# AlphanumericDisplay.net
KiCad netlist of a schematic drawn in EAGLE
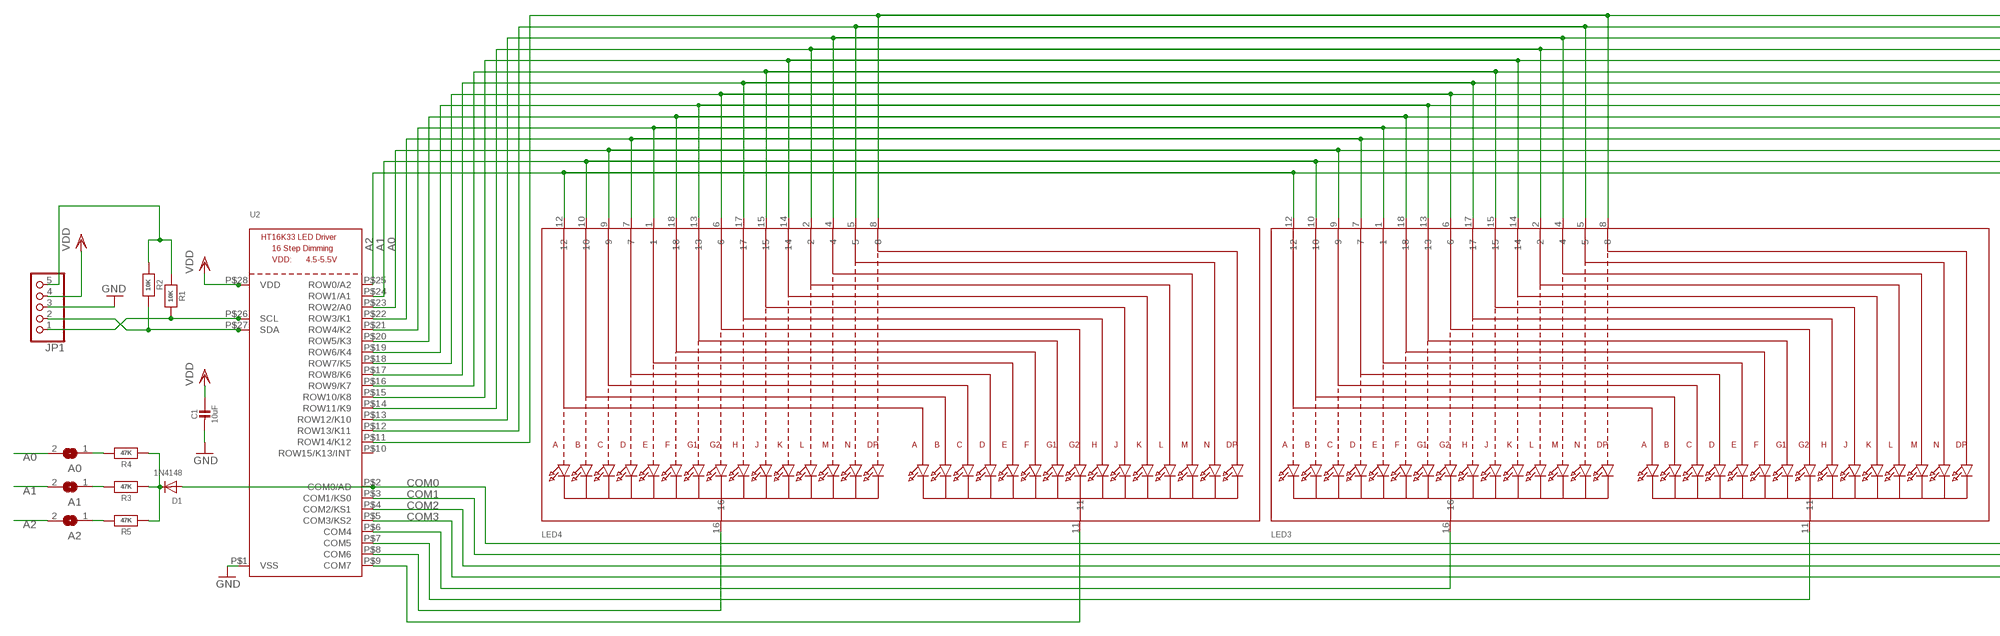
[diagram p0: schematic, sheet 1, part 1 of 2]
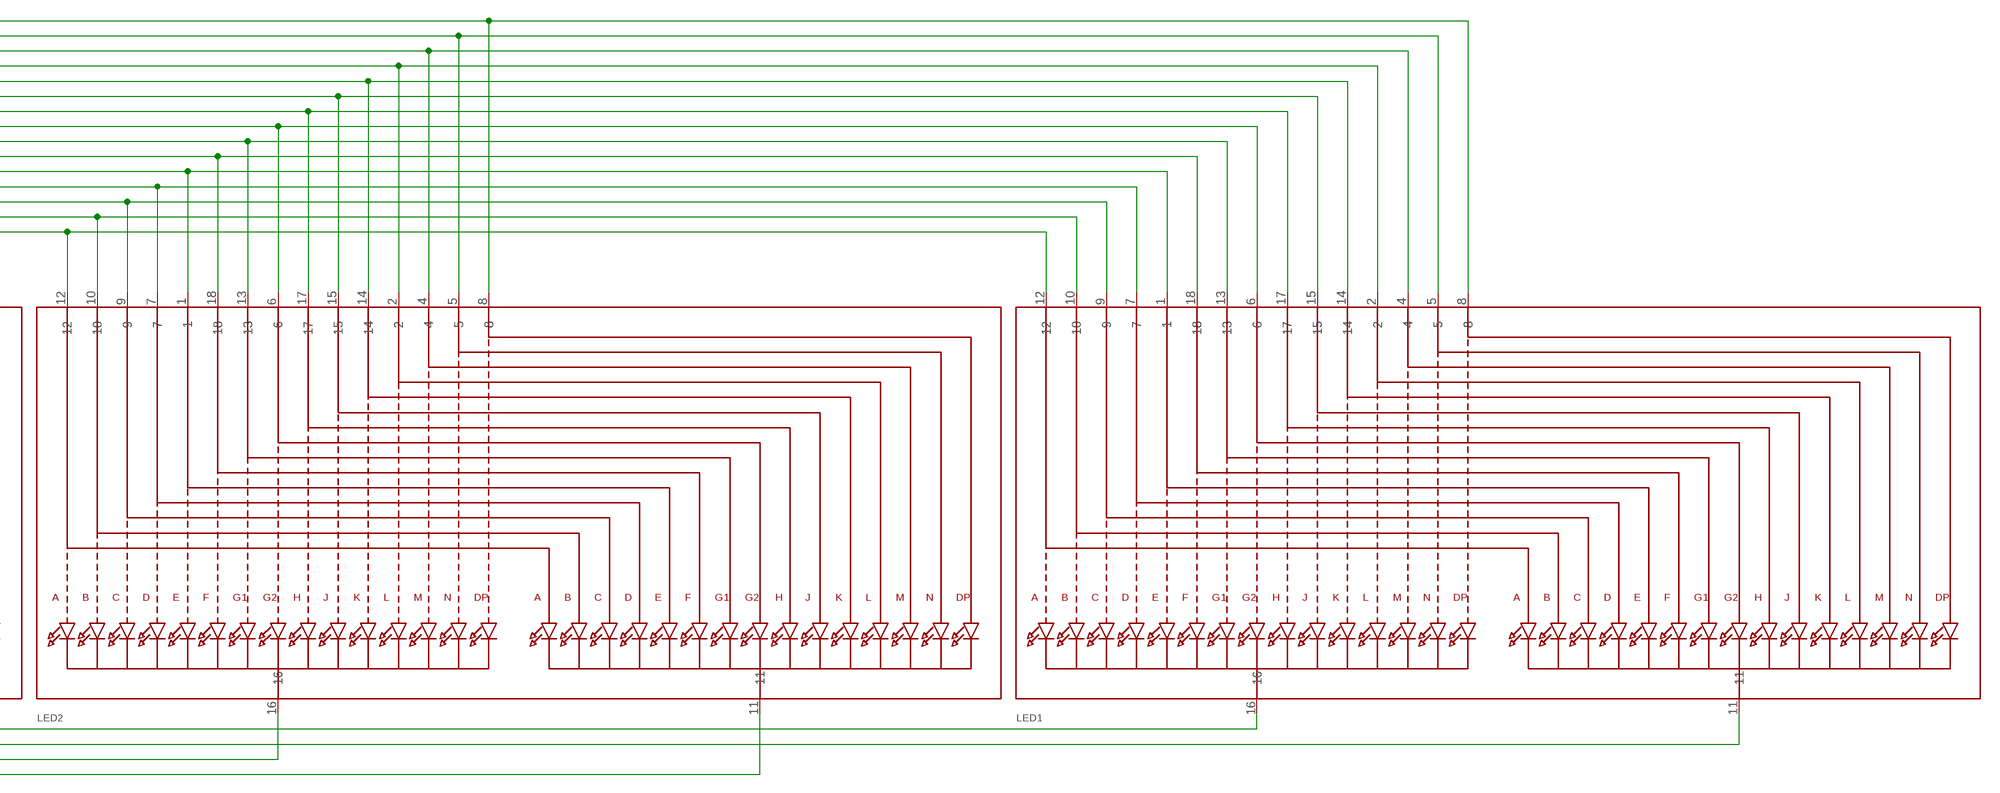
[diagram p1: schematic, sheet 1, part 2 of 2]

(export (version "E")
  (design (tool "Eeschema 10.0.6"))
  (components
    (comp (ref "A0")
      (value "SOLDERJUMPERREFLOW_NOPASTE")
      (footprint "eagle-import:SOLDERJUMPER_REFLOW_NOPASTE")
      (libsource (lib "eagle-import") (part "SOLDERJUMPERREFLOW_NOPASTE"))
    )
    (comp (ref "A1")
      (value "SOLDERJUMPERREFLOW_NOPASTE")
      (footprint "eagle-import:SOLDERJUMPER_REFLOW_NOPASTE")
      (libsource (lib "eagle-import") (part "SOLDERJUMPERREFLOW_NOPASTE"))
    )
    (comp (ref "A2")
      (value "SOLDERJUMPERREFLOW_NOPASTE")
      (footprint "eagle-import:SOLDERJUMPER_REFLOW_NOPASTE")
      (libsource (lib "eagle-import") (part "SOLDERJUMPERREFLOW_NOPASTE"))
    )
    (comp (ref "C1")
      (value "10uF")
      (footprint "eagle-import:0805-NO")
      (libsource (lib "eagle-import") (part "CAP_CERAMIC0805-NOOUTLINE"))
    )
    (comp (ref "D1")
      (value "1N4148")
      (footprint "eagle-import:SOD-323F")
      (libsource (lib "eagle-import") (part "DIODESOD-323F"))
    )
    (comp (ref "JP1")
      (value "HEADER-1X570MIL")
      (footprint "eagle-import:1X05_ROUND_70")
      (libsource (lib "eagle-import") (part "HEADER-1X570MIL"))
    )
    (comp (ref "LED1")
      (value "DISP_SEGMENT_STARBURST_DUAL_COMMONCATHODE")
      (footprint "eagle-import:SEGMENT_STARTBUST_DUAL_KWA-541CBB")
      (libsource (lib "eagle-import") (part "DISP_SEGMENT_STARBURST_DUAL_COMMONCATHODE"))
    )
    (comp (ref "LED2")
      (value "DISP_SEGMENT_STARBURST_DUAL_COMMONCATHODE")
      (footprint "eagle-import:SEGMENT_STARTBUST_DUAL_KWA-541CBB")
      (libsource (lib "eagle-import") (part "DISP_SEGMENT_STARBURST_DUAL_COMMONCATHODE"))
    )
    (comp (ref "LED3")
      (value "DISP_SEGMENT_STARBURST_DUAL_COMMONCATHODE")
      (footprint "eagle-import:SEGMENT_STARTBUST_DUAL_KWA-541CBB")
      (libsource (lib "eagle-import") (part "DISP_SEGMENT_STARBURST_DUAL_COMMONCATHODE"))
    )
    (comp (ref "LED4")
      (value "DISP_SEGMENT_STARBURST_DUAL_COMMONCATHODE")
      (footprint "eagle-import:SEGMENT_STARTBUST_DUAL_KWA-541CBB")
      (libsource (lib "eagle-import") (part "DISP_SEGMENT_STARBURST_DUAL_COMMONCATHODE"))
    )
    (comp (ref "R1")
      (value "10K")
      (footprint "eagle-import:0805-NO")
      (libsource (lib "eagle-import") (part "RESISTOR0805_NOOUTLINE"))
    )
    (comp (ref "R2")
      (value "10K")
      (footprint "eagle-import:0805-NO")
      (libsource (lib "eagle-import") (part "RESISTOR0805_NOOUTLINE"))
    )
    (comp (ref "R3")
      (value "47K")
      (footprint "eagle-import:0805-NO")
      (libsource (lib "eagle-import") (part "RESISTOR0805_NOOUTLINE"))
    )
    (comp (ref "R4")
      (value "47K")
      (footprint "eagle-import:0805-NO")
      (libsource (lib "eagle-import") (part "RESISTOR0805_NOOUTLINE"))
    )
    (comp (ref "R5")
      (value "47K")
      (footprint "eagle-import:0805-NO")
      (libsource (lib "eagle-import") (part "RESISTOR0805_NOOUTLINE"))
    )
    (comp (ref "U2")
      (value "HT16K33_SOP28")
      (footprint "eagle-import:SOP28_300MIL")
      (libsource (lib "eagle-import") (part "HT16K33_SOP28"))
    )
  )
  (nets
    (net (code "1") (name "/A0") (class "Default")
      (node (ref "A0") (pin "2") (pinfunction "2_2") (pintype "passive"))
      (node (ref "LED1") (pin "9") (pinfunction "9_9") (pintype "bidirectional"))
      (node (ref "LED2") (pin "9") (pinfunction "9_9") (pintype "bidirectional"))
      (node (ref "LED3") (pin "9") (pinfunction "9_9") (pintype "bidirectional"))
      (node (ref "LED4") (pin "9") (pinfunction "9_9") (pintype "bidirectional"))
      (node (ref "U2") (pin "P$23") (pinfunction "ROW2/A0_P$23") (pintype "bidirectional"))
    )
    (net (code "2") (name "/A1") (class "Default")
      (node (ref "A1") (pin "2") (pinfunction "2_2") (pintype "passive"))
      (node (ref "LED1") (pin "10") (pinfunction "10_10") (pintype "bidirectional"))
      (node (ref "LED2") (pin "10") (pinfunction "10_10") (pintype "bidirectional"))
      (node (ref "LED3") (pin "10") (pinfunction "10_10") (pintype "bidirectional"))
      (node (ref "LED4") (pin "10") (pinfunction "10_10") (pintype "bidirectional"))
      (node (ref "U2") (pin "P$24") (pinfunction "ROW1/A1_P$24") (pintype "bidirectional"))
    )
    (net (code "3") (name "/A2") (class "Default")
      (node (ref "A2") (pin "2") (pinfunction "2_2") (pintype "passive"))
      (node (ref "LED1") (pin "12") (pinfunction "12_12") (pintype "bidirectional"))
      (node (ref "LED2") (pin "12") (pinfunction "12_12") (pintype "bidirectional"))
      (node (ref "LED3") (pin "12") (pinfunction "12_12") (pintype "bidirectional"))
      (node (ref "LED4") (pin "12") (pinfunction "12_12") (pintype "bidirectional"))
      (node (ref "U2") (pin "P$25") (pinfunction "ROW0/A2_P$25") (pintype "bidirectional"))
    )
    (net (code "4") (name "/COM0") (class "Default")
      (node (ref "D1") (pin "A") (pinfunction "A_A") (pintype "passive"))
      (node (ref "LED1") (pin "16") (pinfunction "16_16") (pintype "bidirectional"))
      (node (ref "U2") (pin "P$2") (pinfunction "COM0/AD_P$2") (pintype "bidirectional"))
    )
    (net (code "5") (name "/COM1") (class "Default")
      (node (ref "LED1") (pin "11") (pinfunction "11_11") (pintype "bidirectional"))
      (node (ref "U2") (pin "P$3") (pinfunction "COM1/KS0_P$3") (pintype "bidirectional"))
    )
    (net (code "6") (name "/COM2") (class "Default")
      (node (ref "LED2") (pin "16") (pinfunction "16_16") (pintype "bidirectional"))
      (node (ref "U2") (pin "P$4") (pinfunction "COM2/KS1_P$4") (pintype "bidirectional"))
    )
    (net (code "7") (name "/COM3") (class "Default")
      (node (ref "LED2") (pin "11") (pinfunction "11_11") (pintype "bidirectional"))
      (node (ref "U2") (pin "P$5") (pinfunction "COM3/KS2_P$5") (pintype "bidirectional"))
    )
    (net (code "8") (name "GND") (class "Default")
      (node (ref "C1") (pin "2") (pinfunction "2_2") (pintype "passive"))
      (node (ref "JP1") (pin "3") (pinfunction "3_3") (pintype "passive"))
      (node (ref "U2") (pin "P$1") (pinfunction "VSS_P$1") (pintype "bidirectional"))
    )
    (net (code "9") (name "Net-(A0-Pad1)") (class "Default")
      (node (ref "A0") (pin "1") (pinfunction "1_1") (pintype "passive"))
      (node (ref "R4") (pin "2") (pinfunction "2_2") (pintype "passive"))
    )
    (net (code "10") (name "Net-(A1-Pad1)") (class "Default")
      (node (ref "A1") (pin "1") (pinfunction "1_1") (pintype "passive"))
      (node (ref "R3") (pin "2") (pinfunction "2_2") (pintype "passive"))
    )
    (net (code "11") (name "Net-(A2-Pad1)") (class "Default")
      (node (ref "A2") (pin "1") (pinfunction "1_1") (pintype "passive"))
      (node (ref "R5") (pin "2") (pinfunction "2_2") (pintype "passive"))
    )
    (net (code "12") (name "Net-(D1-PadC)") (class "Default")
      (node (ref "D1") (pin "C") (pinfunction "C_C") (pintype "passive"))
      (node (ref "R3") (pin "1") (pinfunction "1_1") (pintype "passive"))
      (node (ref "R4") (pin "1") (pinfunction "1_1") (pintype "passive"))
      (node (ref "R5") (pin "1") (pinfunction "1_1") (pintype "passive"))
    )
    (net (code "13") (name "Net-(JP1-Pad5)") (class "Default")
      (node (ref "JP1") (pin "5") (pinfunction "5_5") (pintype "passive"))
      (node (ref "R1") (pin "1") (pinfunction "1_1") (pintype "passive"))
      (node (ref "R2") (pin "1") (pinfunction "1_1") (pintype "passive"))
    )
    (net (code "14") (name "Net-(U2-COM4)") (class "Default")
      (node (ref "LED3") (pin "16") (pinfunction "16_16") (pintype "bidirectional"))
      (node (ref "U2") (pin "P$6") (pinfunction "COM4_P$6") (pintype "bidirectional"))
    )
    (net (code "15") (name "Net-(U2-COM5)") (class "Default")
      (node (ref "LED3") (pin "11") (pinfunction "11_11") (pintype "bidirectional"))
      (node (ref "U2") (pin "P$7") (pinfunction "COM5_P$7") (pintype "bidirectional"))
    )
    (net (code "16") (name "Net-(U2-COM6)") (class "Default")
      (node (ref "LED4") (pin "16") (pinfunction "16_16") (pintype "bidirectional"))
      (node (ref "U2") (pin "P$8") (pinfunction "COM6_P$8") (pintype "bidirectional"))
    )
    (net (code "17") (name "Net-(U2-COM7)") (class "Default")
      (node (ref "LED4") (pin "11") (pinfunction "11_11") (pintype "bidirectional"))
      (node (ref "U2") (pin "P$9") (pinfunction "COM7_P$9") (pintype "bidirectional"))
    )
    (net (code "18") (name "Net-(U2-ROW3{slash}K1)") (class "Default")
      (node (ref "LED1") (pin "7") (pinfunction "7_7") (pintype "bidirectional"))
      (node (ref "LED2") (pin "7") (pinfunction "7_7") (pintype "bidirectional"))
      (node (ref "LED3") (pin "7") (pinfunction "7_7") (pintype "bidirectional"))
      (node (ref "LED4") (pin "7") (pinfunction "7_7") (pintype "bidirectional"))
      (node (ref "U2") (pin "P$22") (pinfunction "ROW3/K1_P$22") (pintype "bidirectional"))
    )
    (net (code "19") (name "Net-(U2-ROW4{slash}K2)") (class "Default")
      (node (ref "LED1") (pin "1") (pinfunction "1_1") (pintype "bidirectional"))
      (node (ref "LED2") (pin "1") (pinfunction "1_1") (pintype "bidirectional"))
      (node (ref "LED3") (pin "1") (pinfunction "1_1") (pintype "bidirectional"))
      (node (ref "LED4") (pin "1") (pinfunction "1_1") (pintype "bidirectional"))
      (node (ref "U2") (pin "P$21") (pinfunction "ROW4/K2_P$21") (pintype "bidirectional"))
    )
    (net (code "20") (name "Net-(U2-ROW5{slash}K3)") (class "Default")
      (node (ref "LED1") (pin "18") (pinfunction "18_18") (pintype "bidirectional"))
      (node (ref "LED2") (pin "18") (pinfunction "18_18") (pintype "bidirectional"))
      (node (ref "LED3") (pin "18") (pinfunction "18_18") (pintype "bidirectional"))
      (node (ref "LED4") (pin "18") (pinfunction "18_18") (pintype "bidirectional"))
      (node (ref "U2") (pin "P$20") (pinfunction "ROW5/K3_P$20") (pintype "bidirectional"))
    )
    (net (code "21") (name "Net-(U2-ROW6{slash}K4)") (class "Default")
      (node (ref "LED1") (pin "13") (pinfunction "13_13") (pintype "bidirectional"))
      (node (ref "LED2") (pin "13") (pinfunction "13_13") (pintype "bidirectional"))
      (node (ref "LED3") (pin "13") (pinfunction "13_13") (pintype "bidirectional"))
      (node (ref "LED4") (pin "13") (pinfunction "13_13") (pintype "bidirectional"))
      (node (ref "U2") (pin "P$19") (pinfunction "ROW6/K4_P$19") (pintype "bidirectional"))
    )
    (net (code "22") (name "Net-(U2-ROW7{slash}K5)") (class "Default")
      (node (ref "LED1") (pin "6") (pinfunction "6_6") (pintype "bidirectional"))
      (node (ref "LED2") (pin "6") (pinfunction "6_6") (pintype "bidirectional"))
      (node (ref "LED3") (pin "6") (pinfunction "6_6") (pintype "bidirectional"))
      (node (ref "LED4") (pin "6") (pinfunction "6_6") (pintype "bidirectional"))
      (node (ref "U2") (pin "P$18") (pinfunction "ROW7/K5_P$18") (pintype "bidirectional"))
    )
    (net (code "23") (name "Net-(U2-ROW8{slash}K6)") (class "Default")
      (node (ref "LED1") (pin "17") (pinfunction "17_17") (pintype "bidirectional"))
      (node (ref "LED2") (pin "17") (pinfunction "17_17") (pintype "bidirectional"))
      (node (ref "LED3") (pin "17") (pinfunction "17_17") (pintype "bidirectional"))
      (node (ref "LED4") (pin "17") (pinfunction "17_17") (pintype "bidirectional"))
      (node (ref "U2") (pin "P$17") (pinfunction "ROW8/K6_P$17") (pintype "bidirectional"))
    )
    (net (code "24") (name "Net-(U2-ROW9{slash}K7)") (class "Default")
      (node (ref "LED1") (pin "15") (pinfunction "15_15") (pintype "bidirectional"))
      (node (ref "LED2") (pin "15") (pinfunction "15_15") (pintype "bidirectional"))
      (node (ref "LED3") (pin "15") (pinfunction "15_15") (pintype "bidirectional"))
      (node (ref "LED4") (pin "15") (pinfunction "15_15") (pintype "bidirectional"))
      (node (ref "U2") (pin "P$16") (pinfunction "ROW9/K7_P$16") (pintype "bidirectional"))
    )
    (net (code "25") (name "Net-(U2-ROW10{slash}K8)") (class "Default")
      (node (ref "LED1") (pin "14") (pinfunction "14_14") (pintype "bidirectional"))
      (node (ref "LED2") (pin "14") (pinfunction "14_14") (pintype "bidirectional"))
      (node (ref "LED3") (pin "14") (pinfunction "14_14") (pintype "bidirectional"))
      (node (ref "LED4") (pin "14") (pinfunction "14_14") (pintype "bidirectional"))
      (node (ref "U2") (pin "P$15") (pinfunction "ROW10/K8_P$15") (pintype "bidirectional"))
    )
    (net (code "26") (name "Net-(U2-ROW11{slash}K9)") (class "Default")
      (node (ref "LED1") (pin "2") (pinfunction "2_2") (pintype "bidirectional"))
      (node (ref "LED2") (pin "2") (pinfunction "2_2") (pintype "bidirectional"))
      (node (ref "LED3") (pin "2") (pinfunction "2_2") (pintype "bidirectional"))
      (node (ref "LED4") (pin "2") (pinfunction "2_2") (pintype "bidirectional"))
      (node (ref "U2") (pin "P$14") (pinfunction "ROW11/K9_P$14") (pintype "bidirectional"))
    )
    (net (code "27") (name "Net-(U2-ROW12{slash}K10)") (class "Default")
      (node (ref "LED1") (pin "4") (pinfunction "4_4") (pintype "bidirectional"))
      (node (ref "LED2") (pin "4") (pinfunction "4_4") (pintype "bidirectional"))
      (node (ref "LED3") (pin "4") (pinfunction "4_4") (pintype "bidirectional"))
      (node (ref "LED4") (pin "4") (pinfunction "4_4") (pintype "bidirectional"))
      (node (ref "U2") (pin "P$13") (pinfunction "ROW12/K10_P$13") (pintype "bidirectional"))
    )
    (net (code "28") (name "Net-(U2-ROW13{slash}K11)") (class "Default")
      (node (ref "LED1") (pin "5") (pinfunction "5_5") (pintype "bidirectional"))
      (node (ref "LED2") (pin "5") (pinfunction "5_5") (pintype "bidirectional"))
      (node (ref "LED3") (pin "5") (pinfunction "5_5") (pintype "bidirectional"))
      (node (ref "LED4") (pin "5") (pinfunction "5_5") (pintype "bidirectional"))
      (node (ref "U2") (pin "P$12") (pinfunction "ROW13/K11_P$12") (pintype "bidirectional"))
    )
    (net (code "29") (name "Net-(U2-ROW14{slash}K12)") (class "Default")
      (node (ref "LED1") (pin "8") (pinfunction "8_8") (pintype "bidirectional"))
      (node (ref "LED2") (pin "8") (pinfunction "8_8") (pintype "bidirectional"))
      (node (ref "LED3") (pin "8") (pinfunction "8_8") (pintype "bidirectional"))
      (node (ref "LED4") (pin "8") (pinfunction "8_8") (pintype "bidirectional"))
      (node (ref "U2") (pin "P$11") (pinfunction "ROW14/K12_P$11") (pintype "bidirectional"))
    )
    (net (code "30") (name "Net-(U2-SCL)") (class "Default")
      (node (ref "JP1") (pin "1") (pinfunction "1_1") (pintype "passive"))
      (node (ref "R1") (pin "2") (pinfunction "2_2") (pintype "passive"))
      (node (ref "U2") (pin "P$26") (pinfunction "SCL_P$26") (pintype "bidirectional"))
    )
    (net (code "31") (name "Net-(U2-SDA)") (class "Default")
      (node (ref "JP1") (pin "2") (pinfunction "2_2") (pintype "passive"))
      (node (ref "R2") (pin "2") (pinfunction "2_2") (pintype "passive"))
      (node (ref "U2") (pin "P$27") (pinfunction "SDA_P$27") (pintype "bidirectional"))
    )
    (net (code "32") (name "VDD") (class "Default")
      (node (ref "C1") (pin "1") (pinfunction "1_1") (pintype "passive"))
      (node (ref "JP1") (pin "4") (pinfunction "4_4") (pintype "passive"))
      (node (ref "U2") (pin "P$28") (pinfunction "VDD_P$28") (pintype "bidirectional"))
    )
    (net (code "33") (name "unconnected-(U2-ROW15{slash}K13{slash}INT-PadP$10)") (class "Default")
      (node (ref "U2") (pin "P$10") (pinfunction "ROW15/K13/INT_P$10") (pintype "bidirectional"))
    )
  )
)
